# AIRDC.net
KiCad netlist of a schematic drawn in EAGLE
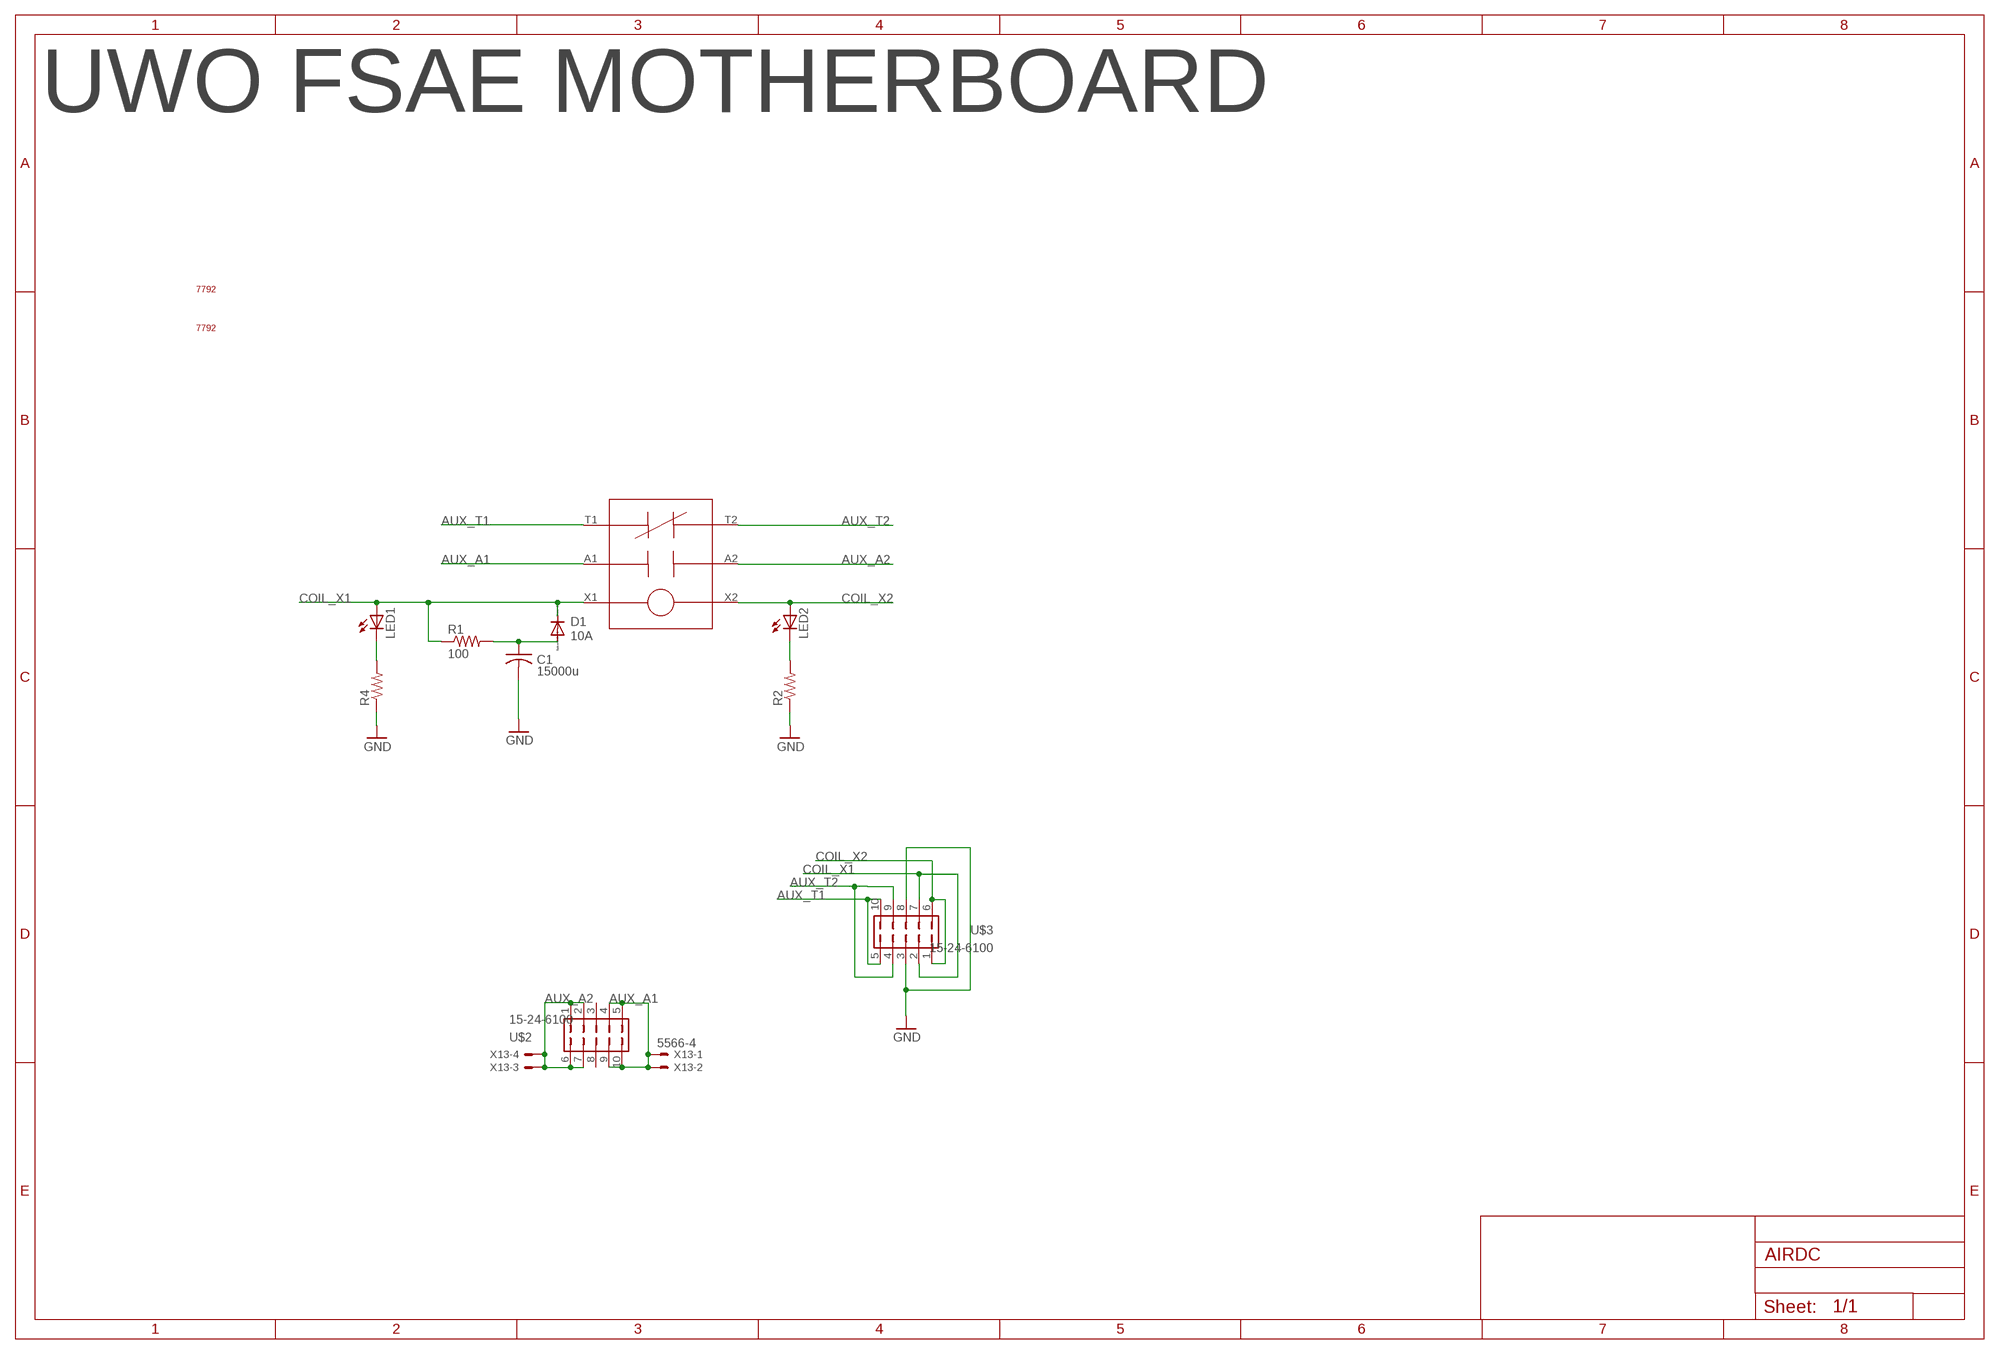
[diagram p0: schematic, sheet 1]

(export (version "E")
  (design (tool "Eeschema 10.0.6"))
  (components
    (comp (ref "C1")
      (value "15000u")
      (footprint "eagle-import:CAPPRD750W65D1800H3700B")
      (libsource (lib "eagle-import") (part "AIR_HOLDUP_CAP"))
    )
    (comp (ref "D1")
      (value "10A")
      (footprint "eagle-import:DIOAD1570W120L850D500B")
      (libsource (lib "eagle-import") (part "AIR_HOLDUP_DIODE"))
    )
    (comp (ref "LED1")
      (value "LED3MM")
      (footprint "eagle-import:LED3MM")
      (libsource (lib "eagle-import") (part "LED3MM"))
    )
    (comp (ref "LED2")
      (value "LED3MM")
      (footprint "eagle-import:LED3MM")
      (libsource (lib "eagle-import") (part "LED3MM"))
    )
    (comp (ref "R1")
      (value "100")
      (footprint "eagle-import:RESAD976W63L650D250B")
      (libsource (lib "eagle-import") (part "AIR_HOLDUP_RESISTOR"))
    )
    (comp (ref "R2")
      (value "R-US_R0805")
      (footprint "eagle-import:R0805")
      (libsource (lib "eagle-import") (part "R-US_R0805"))
    )
    (comp (ref "R4")
      (value "R-US_R0805")
      (footprint "eagle-import:R0805")
      (libsource (lib "eagle-import") (part "R-US_R0805"))
    )
    (comp (ref "U$1")
      (value "GV224")
      (footprint "eagle-import:GV224")
      (libsource (lib "eagle-import") (part "GV224"))
    )
    (comp (ref "U$2")
      (value "15-24-6100")
      (footprint "eagle-import:15-24-6100")
      (libsource (lib "eagle-import") (part "15-24-6100"))
    )
    (comp (ref "U$3")
      (value "15-24-6100")
      (footprint "eagle-import:15-24-6100")
      (libsource (lib "eagle-import") (part "15-24-6100"))
    )
    (comp (ref "U$4")
      (value "7792")
      (footprint "eagle-import:7792")
      (libsource (lib "eagle-import") (part "7792"))
    )
    (comp (ref "U$5")
      (value "7792")
      (footprint "eagle-import:7792")
      (libsource (lib "eagle-import") (part "7792"))
    )
    (comp (ref "X13")
      (value "5566-4")
      (footprint "eagle-import:5566-4")
      (fields (field (name "MF") "MOLEX"))
      (libsource (lib "eagle-import") (part "5566-4"))
    )
  )
  (nets
    (net (code "1") (name "/AUX_A1") (class "Default")
      (node (ref "U$1") (pin "A1") (pinfunction "A1_A1") (pintype "bidirectional"))
      (node (ref "U$2") (pin "10") (pinfunction "10_10") (pintype "passive"))
      (node (ref "U$2") (pin "4") (pinfunction "4_4") (pintype "passive"))
      (node (ref "U$2") (pin "5") (pinfunction "5_5") (pintype "passive"))
      (node (ref "U$2") (pin "9") (pinfunction "9_9") (pintype "passive"))
      (node (ref "X13") (pin "1") (pinfunction "S_1") (pintype "passive"))
      (node (ref "X13") (pin "2") (pinfunction "S_2") (pintype "passive"))
    )
    (net (code "2") (name "/AUX_A2") (class "Default")
      (node (ref "U$1") (pin "A2") (pinfunction "A2_A2") (pintype "bidirectional"))
      (node (ref "U$2") (pin "1") (pinfunction "1_1") (pintype "passive"))
      (node (ref "U$2") (pin "2") (pinfunction "2_2") (pintype "passive"))
      (node (ref "U$2") (pin "6") (pinfunction "6_6") (pintype "passive"))
      (node (ref "U$2") (pin "7") (pinfunction "7_7") (pintype "passive"))
      (node (ref "X13") (pin "3") (pinfunction "S_3") (pintype "passive"))
      (node (ref "X13") (pin "4") (pinfunction "S_4") (pintype "passive"))
    )
    (net (code "3") (name "/AUX_T1") (class "Default")
      (node (ref "U$1") (pin "T1") (pinfunction "T1_T1") (pintype "bidirectional"))
      (node (ref "U$3") (pin "10") (pinfunction "10_10") (pintype "passive"))
      (node (ref "U$3") (pin "5") (pinfunction "5_5") (pintype "passive"))
    )
    (net (code "4") (name "/AUX_T2") (class "Default")
      (node (ref "U$1") (pin "T2") (pinfunction "T2_T2") (pintype "bidirectional"))
      (node (ref "U$3") (pin "4") (pinfunction "4_4") (pintype "passive"))
      (node (ref "U$3") (pin "9") (pinfunction "9_9") (pintype "passive"))
    )
    (net (code "5") (name "/COIL_X1") (class "Default")
      (node (ref "D1") (pin "1") (pinfunction "C_1") (pintype "passive"))
      (node (ref "LED1") (pin "A") (pinfunction "A_A") (pintype "passive"))
      (node (ref "R1") (pin "1") (pinfunction "1_1") (pintype "passive"))
      (node (ref "U$1") (pin "X1") (pinfunction "X1_X1") (pintype "bidirectional"))
      (node (ref "U$3") (pin "2") (pinfunction "2_2") (pintype "passive"))
      (node (ref "U$3") (pin "7") (pinfunction "7_7") (pintype "passive"))
    )
    (net (code "6") (name "/COIL_X2") (class "Default")
      (node (ref "LED2") (pin "A") (pinfunction "A_A") (pintype "passive"))
      (node (ref "U$1") (pin "X2") (pinfunction "X2_X2") (pintype "bidirectional"))
      (node (ref "U$3") (pin "1") (pinfunction "1_1") (pintype "passive"))
      (node (ref "U$3") (pin "6") (pinfunction "6_6") (pintype "passive"))
    )
    (net (code "7") (name "GND") (class "Default")
      (node (ref "C1") (pin "2") (pinfunction "2_2") (pintype "passive"))
      (node (ref "R2") (pin "1") (pinfunction "1_1") (pintype "passive"))
      (node (ref "R4") (pin "1") (pinfunction "1_1") (pintype "passive"))
      (node (ref "U$3") (pin "3") (pinfunction "3_3") (pintype "passive"))
      (node (ref "U$3") (pin "8") (pinfunction "8_8") (pintype "passive"))
    )
    (net (code "8") (name "Net-(D1-A)") (class "Default")
      (node (ref "C1") (pin "1") (pinfunction "1_1") (pintype "passive"))
      (node (ref "D1") (pin "2") (pinfunction "A_2") (pintype "passive"))
      (node (ref "R1") (pin "2") (pinfunction "2_2") (pintype "passive"))
    )
    (net (code "9") (name "Net-(LED1-C)") (class "Default")
      (node (ref "LED1") (pin "K") (pinfunction "C_K") (pintype "passive"))
      (node (ref "R4") (pin "2") (pinfunction "2_2") (pintype "passive"))
    )
    (net (code "10") (name "Net-(LED2-C)") (class "Default")
      (node (ref "LED2") (pin "K") (pinfunction "C_K") (pintype "passive"))
      (node (ref "R2") (pin "2") (pinfunction "2_2") (pintype "passive"))
    )
    (net (code "11") (name "unconnected-(U$2-Pad3)") (class "Default")
      (node (ref "U$2") (pin "3") (pinfunction "3_3") (pintype "passive"))
    )
    (net (code "12") (name "unconnected-(U$2-Pad8)") (class "Default")
      (node (ref "U$2") (pin "8") (pinfunction "8_8") (pintype "passive"))
    )
  )
)
